# ISO_Power.net
KiCad netlist of a schematic drawn in Altium Designer
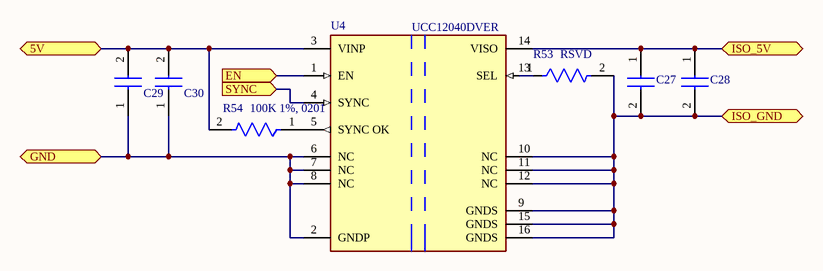
[diagram p0: ISO_Power.SchDoc]

(export (version "E")
  (design (tool "Eeschema 10.0.6"))
  (components
    (comp (ref "C27")
      (value "100 nF, 25V, X6S, 0201")
      (footprint "SamacSys:CAPC0603X33N")
      (description "Capacitor")
      (fields
        (field (name "MANUFACTURER_PART_NUMBER") "GRM033C81E104KE14D")
        (field (name "MOUSER PART NUMBER") "81-GRM33C81E104KE14D")
      )
      (libsource (lib "*") (part "GRM033C81E104KE14D"))
    )
    (comp (ref "C28")
      (value "10 uF, 25V, X6S, 0402")
      (footprint "SamacSys:CAPC1005X70N")
      (description "Capacitor")
      (fields
        (field (name "MANUFACTURER_PART_NUMBER") "GRM155F51E104ZA01E")
        (field (name "MOUSER PART NUMBER") "81-GRM15F51E104ZA01E")
      )
      (libsource (lib "*") (part "GRM155F51E104ZA01E"))
    )
    (comp (ref "C29")
      (value "10 uF, 25V, X6S, 0402")
      (footprint "SamacSys:CAPC1005X70N")
      (description "Capacitor")
      (fields
        (field (name "MANUFACTURER_PART_NUMBER") "GRM155F51E104ZA01E")
        (field (name "MOUSER PART NUMBER") "81-GRM15F51E104ZA01E")
      )
      (libsource (lib "*") (part "GRM155F51E104ZA01E"))
    )
    (comp (ref "C30")
      (value "100 nF, 25V, X6S, 0201")
      (footprint "SamacSys:CAPC0603X33N")
      (description "Capacitor")
      (fields
        (field (name "MANUFACTURER_PART_NUMBER") "GRM033C81E104KE14D")
        (field (name "MOUSER PART NUMBER") "81-GRM33C81E104KE14D")
      )
      (libsource (lib "*") (part "GRM033C81E104KE14D"))
    )
    (comp (ref "R53")
      (value "RSVD")
      (footprint "FP-ERJ1GN-IPC_A")
      (description "RES SMD 100K OHM 1% 1/20W 0201")
      (fields (field (name "TOLERANCE") "1%"))
      (libsource (lib "Altium Content Vault") (part "1029c3af85768c4190bb7ad29bc67b5"))
    )
    (comp (ref "R54")
      (value "100K 1%, 0201")
      (footprint "FP-ERJ1GN-IPC_A")
      (description "RES SMD 100K OHM 1% 1/20W 0201")
      (fields (field (name "TOLERANCE") "1%"))
      (libsource (lib "Altium Content Vault") (part "1029c3af85768c4190bb7ad29bc67b5"))
    )
    (comp (ref "U4")
      (value "UCC12040DVER")
      (footprint "FP-DVE0016A-MFG")
      (description "DC DC CONVERTER 3.3V 5V 500MW")
      (libsource (lib "Altium Content Vault") (part "cf9dcfd4a8b3775ff5e4cba6f3e7206"))
    )
  )
  (nets
    (net (code "1") (name "/5V") (class "Default")
      (node (ref "C29") (pin "2") (pinfunction "2_2") (pintype "passive"))
      (node (ref "C30") (pin "2") (pinfunction "2_2") (pintype "passive"))
      (node (ref "R54") (pin "2") (pinfunction "2_2") (pintype "passive"))
      (node (ref "U4") (pin "3") (pinfunction "VINP_3") (pintype "power_in"))
    )
    (net (code "2") (name "/EN") (class "Default")
      (node (ref "U4") (pin "1") (pinfunction "EN_1") (pintype "input"))
    )
    (net (code "3") (name "/GND") (class "Default")
      (node (ref "C29") (pin "1") (pinfunction "1_1") (pintype "passive"))
      (node (ref "C30") (pin "1") (pinfunction "1_1") (pintype "passive"))
      (node (ref "U4") (pin "2") (pinfunction "GNDP_2") (pintype "power_in"))
      (node (ref "U4") (pin "6") (pinfunction "NC_6") (pintype "passive"))
      (node (ref "U4") (pin "7") (pinfunction "NC_7") (pintype "passive"))
      (node (ref "U4") (pin "8") (pinfunction "NC_8") (pintype "passive"))
    )
    (net (code "4") (name "/ISO_5V") (class "Default")
      (node (ref "C27") (pin "1") (pinfunction "1_1") (pintype "passive"))
      (node (ref "C28") (pin "1") (pinfunction "1_1") (pintype "passive"))
      (node (ref "U4") (pin "14") (pinfunction "VISO_14") (pintype "power_in"))
    )
    (net (code "5") (name "/ISO_GND") (class "Default")
      (node (ref "C27") (pin "2") (pinfunction "2_2") (pintype "passive"))
      (node (ref "C28") (pin "2") (pinfunction "2_2") (pintype "passive"))
      (node (ref "R53") (pin "2") (pinfunction "2_2") (pintype "passive"))
      (node (ref "U4") (pin "10") (pinfunction "NC_10") (pintype "passive"))
      (node (ref "U4") (pin "11") (pinfunction "NC_11") (pintype "passive"))
      (node (ref "U4") (pin "12") (pinfunction "NC_12") (pintype "passive"))
      (node (ref "U4") (pin "15") (pinfunction "GNDS_15") (pintype "power_in"))
      (node (ref "U4") (pin "16") (pinfunction "GNDS_16") (pintype "power_in"))
      (node (ref "U4") (pin "9") (pinfunction "GNDS_9") (pintype "power_in"))
    )
    (net (code "6") (name "/SYNC") (class "Default")
      (node (ref "U4") (pin "4") (pinfunction "SYNC_4") (pintype "input"))
    )
    (net (code "7") (name "Net-(U4-SEL)") (class "Default")
      (node (ref "R53") (pin "1") (pinfunction "1_1") (pintype "passive"))
      (node (ref "U4") (pin "13") (pinfunction "SEL_13") (pintype "input"))
    )
    (net (code "8") (name "Net-(U4-SYNC_OK)") (class "Default")
      (node (ref "R54") (pin "1") (pinfunction "1_1") (pintype "passive"))
      (node (ref "U4") (pin "5") (pinfunction "SYNC_OK_5") (pintype "output"))
    )
  )
)
